# Power.net
KiCad netlist of a schematic drawn in Altium Designer
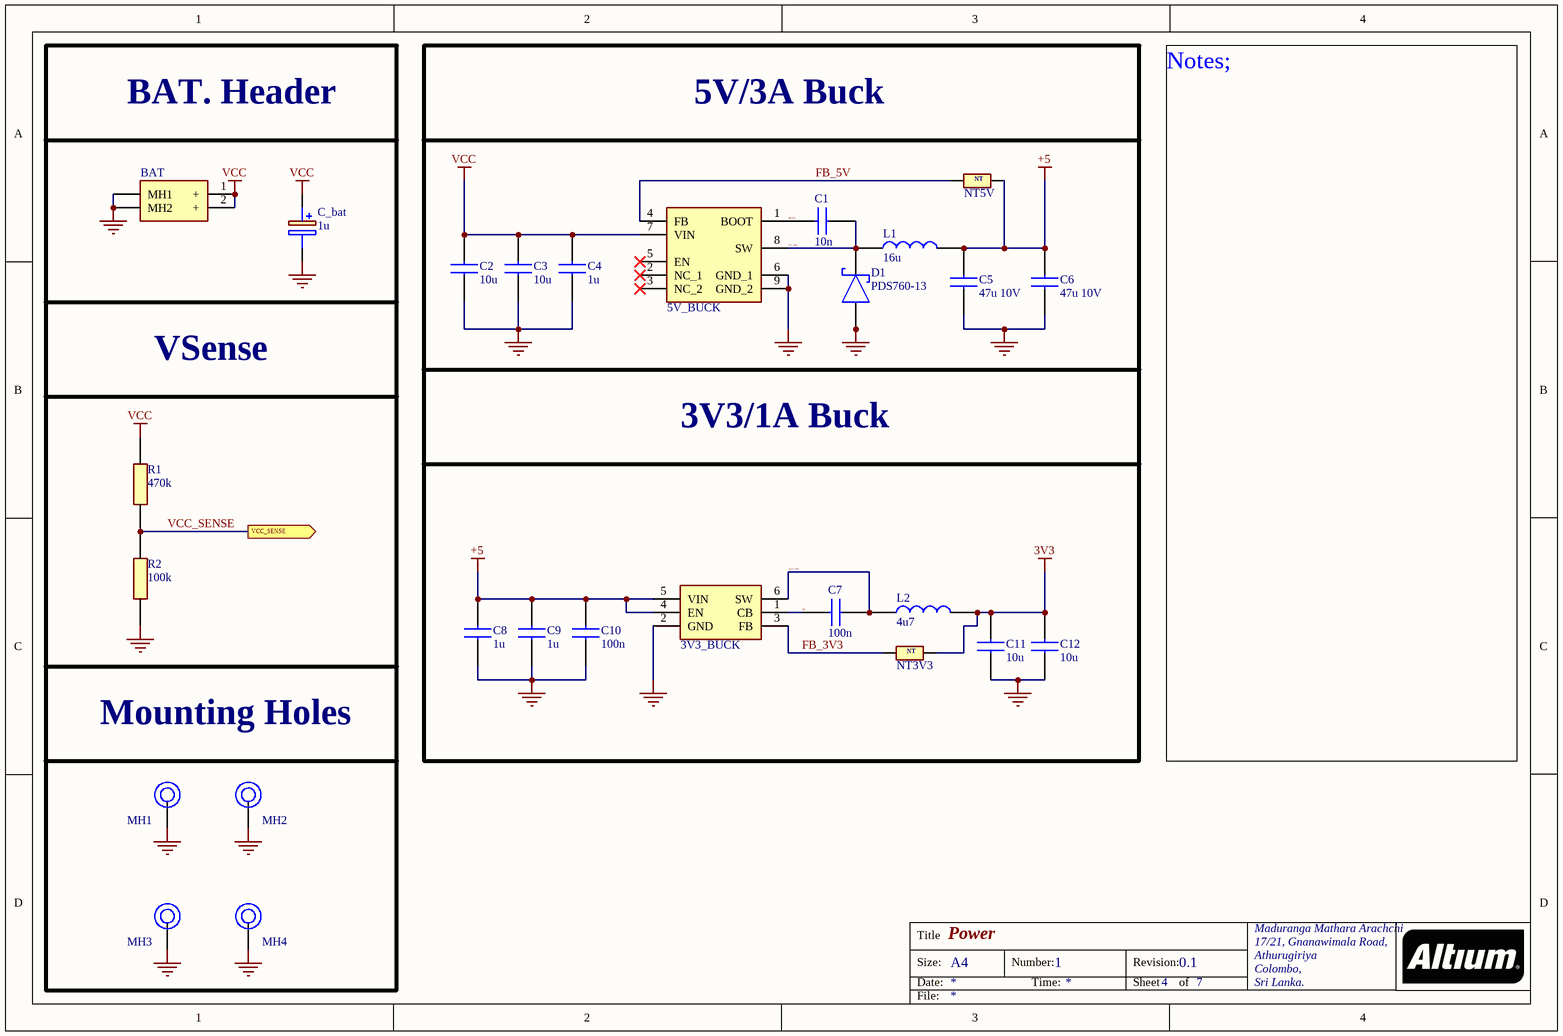
[diagram p0: Power.SchDoc]

(export (version "E")
  (design (tool "Eeschema 10.0.6"))
  (components
    (comp (ref "3V3_BUCK")
      (value "LMR50410Y3FQDBVRQ1")
      (footprint "RC_Car:SOT95P280X145-6N")
      (description "3V3 Buck")
      (fields (field (name "MOUSER PART NUMBER") "595-R50410Y3FQDBVRQ1"))
      (libsource (lib "RC_Car") (part "LMR50410Y3FQDBVRQ1"))
    )
    (comp (ref "5V_BUCK")
      (value "LM22676QMRX-5.0_NOPB")
      (footprint "RC_Car:SOIC127P600X170-9N")
      (description "5V Buck")
      (fields
        (field (name "MANUFACTURER_PART_NUMBER") "LM22676QMRX-5.0/NOPB")
        (field (name "MOUSER PART NUMBER") "926-LM22676QMRX50NPB")
      )
      (libsource (lib "RC_Car") (part "LM22676QMRX-5.0_NOPB"))
    )
    (comp (ref "BAT")
      (value "XT60PW-M")
      (footprint "RC_Car:XT60PWM")
      (description "Power Header")
      (libsource (lib "RC_Car") (part "XT60PW-M"))
    )
    (comp (ref "C1")
      (value "10n")
      (footprint "RC_Car:C0603")
      (description "Capacitor")
      (fields
        (field (name "MANUFACTURER_PART_NUMBER") "C0603C103K5RACTU")
        (field (name "MOUSER PART NUMBER") "80-C0603C103K5R")
      )
      (libsource (lib "RC_Car") (part "C0603C103K5RACTU"))
    )
    (comp (ref "C2")
      (value "10u")
      (footprint "RC_Car:CAPC1608X90N")
      (description "Capacitor")
      (fields (field (name "MANUFACTURER_PART_NUMBER") "C0603C106M9PAC-TU"))
      (libsource (lib "RC_Car") (part "C0603C106M9PAC-TU"))
    )
    (comp (ref "C3")
      (value "10u")
      (footprint "RC_Car:CAPC1608X90N")
      (description "Capacitor")
      (fields (field (name "MANUFACTURER_PART_NUMBER") "C0603C106M9PAC-TU"))
      (libsource (lib "RC_Car") (part "C0603C106M9PAC-TU"))
    )
    (comp (ref "C4")
      (value "1u")
      (footprint "RC_Car:CAPC1608X90N")
      (description "Capacitor")
      (fields
        (field (name "MANUFACTURER_PART_NUMBER") "MSASU168SB5105KTNA01")
        (field (name "MOUSER PART NUMBER") "963-MSASU168SB5105KT")
      )
      (libsource (lib "RC_Car") (part "MSASU168SB5105KTNA01"))
    )
    (comp (ref "C5")
      (value "47u 10V")
      (footprint "RC_Car:GRM32x")
      (description "Capacitor")
      (fields
        (field (name "MANUFACTURER_PART_NUMBER") "GRM32ER71A476KE15L")
        (field (name "MOUSER PART NUMBER") "81-GRM32ER71A476KE5L")
      )
      (libsource (lib "RC_Car") (part "GRM32ER71A476KE15L"))
    )
    (comp (ref "C6")
      (value "47u 10V")
      (footprint "RC_Car:GRM32x")
      (description "Capacitor")
      (fields
        (field (name "MANUFACTURER_PART_NUMBER") "GRM32ER71A476KE15L")
        (field (name "MOUSER PART NUMBER") "81-GRM32ER71A476KE5L")
      )
      (libsource (lib "RC_Car") (part "GRM32ER71A476KE15L"))
    )
    (comp (ref "C7")
      (value "100n")
      (footprint "RC_Car:GRM18x")
      (description "Capacitor")
      (fields
        (field (name "MANUFACTURER_PART_NUMBER") "GRM188R72A104KA35D")
        (field (name "MOUSER PART NUMBER") "81-GRM188R72A104KA35")
      )
      (libsource (lib "RC_Car") (part "GRM188R72A104KA35D"))
    )
    (comp (ref "C8")
      (value "1u")
      (footprint "RC_Car:CAPC1608X90N")
      (description "Capacitor")
      (fields
        (field (name "MANUFACTURER_PART_NUMBER") "MSASU168SB5105KTNA01")
        (field (name "MOUSER PART NUMBER") "963-MSASU168SB5105KT")
      )
      (libsource (lib "RC_Car") (part "MSASU168SB5105KTNA01"))
    )
    (comp (ref "C9")
      (value "1u")
      (footprint "RC_Car:CAPC1608X90N")
      (description "Capacitor")
      (fields
        (field (name "MANUFACTURER_PART_NUMBER") "MSASU168SB5105KTNA01")
        (field (name "MOUSER PART NUMBER") "963-MSASU168SB5105KT")
      )
      (libsource (lib "RC_Car") (part "MSASU168SB5105KTNA01"))
    )
    (comp (ref "C10")
      (value "100n")
      (footprint "RC_Car:GRM18x")
      (description "Capacitor")
      (fields
        (field (name "MANUFACTURER_PART_NUMBER") "GRM188R72A104KA35D")
        (field (name "MOUSER PART NUMBER") "81-GRM188R72A104KA35")
      )
      (libsource (lib "RC_Car") (part "GRM188R72A104KA35D"))
    )
    (comp (ref "C11")
      (value "10u")
      (footprint "RC_Car:CAPC1608X90N")
      (description "Capacitor")
      (fields (field (name "MANUFACTURER_PART_NUMBER") "C0603C106M9PAC-TU"))
      (libsource (lib "RC_Car") (part "C0603C106M9PAC-TU"))
    )
    (comp (ref "C12")
      (value "10u")
      (footprint "RC_Car:CAPC1608X90N")
      (description "Capacitor")
      (fields (field (name "MANUFACTURER_PART_NUMBER") "C0603C106M9PAC-TU"))
      (libsource (lib "RC_Car") (part "C0603C106M9PAC-TU"))
    )
    (comp (ref "C_bat")
      (value "1u")
      (footprint "RC_Car:CAPAE430X550N")
      (description "Capacitor Polarised")
      (fields
        (field (name "MANUFACTURER_PART_NUMBER") "865081740001")
        (field (name "MOUSER PART NUMBER") "710-865081740001")
      )
      (libsource (lib "RC_Car") (part "865081740001"))
    )
    (comp (ref "D1")
      (value "PDS760-13")
      (footprint "RC_Car:PDS76013")
      (description "Schottky Diode")
      (fields (field (name "MOUSER PART NUMBER") "621-PDS760-F"))
      (libsource (lib "RC_Car") (part "PDS760-13"))
    )
    (comp (ref "L1")
      (value "16u")
      (footprint "RC_Car:WE-HCI_105023")
      (description "Inductor")
      (fields
        (field (name "MANUFACTURER_PART_NUMBER") "7443251600")
        (field (name "MOUSER PART NUMBER") "710-7443251600")
      )
      (libsource (lib "RC_Car") (part "7443251600"))
    )
    (comp (ref "L2")
      (value "4u7")
      (footprint "RC_Car:SDR0403")
      (description "Inductor")
      (fields
        (field (name "MANUFACTURER_PART_NUMBER") "SDR0403-4R7ML")
        (field (name "MOUSER PART NUMBER") "652-SDR0403-4R7ML")
      )
      (libsource (lib "RC_Car") (part "SDR0403-4R7ML"))
    )
    (comp (ref "MH1")
      (value "Mounting Hole 2mm")
      (footprint "Mounting Hole")
      (libsource (lib "RC_Car") (part "Mounting Hole 2mm"))
    )
    (comp (ref "MH2")
      (value "Mounting Hole 2mm")
      (footprint "Mounting Hole")
      (libsource (lib "RC_Car") (part "Mounting Hole 2mm"))
    )
    (comp (ref "MH3")
      (value "Mounting Hole 2mm")
      (footprint "Mounting Hole")
      (libsource (lib "RC_Car") (part "Mounting Hole 2mm"))
    )
    (comp (ref "MH4")
      (value "Mounting Hole 2mm")
      (footprint "Mounting Hole")
      (libsource (lib "RC_Car") (part "Mounting Hole 2mm"))
    )
    (comp (ref "NT3V3")
      (value "NetTie_SMD")
      (footprint "NetTie_SMD")
      (libsource (lib "RC_Car") (part "NetTie_SMD"))
    )
    (comp (ref "NT5V")
      (value "NetTie_SMD")
      (footprint "NetTie_SMD")
      (libsource (lib "RC_Car") (part "NetTie_SMD"))
    )
    (comp (ref "R1")
      (value "470k")
      (footprint "RC_Car:ERJP03_PA3_(0603)")
      (description "Resistor")
      (fields
        (field (name "MANUFACTURER_PART_NUMBER") "ERJ-PA3F4703V")
        (field (name "MOUSER PART NUMBER") "667-ERJ-PA3F4703V")
      )
      (libsource (lib "RC_Car") (part "ERJ-PA3F4703V"))
    )
    (comp (ref "R2")
      (value "100k")
      (footprint "RC_Car:ERJP03_PA3_(0603)")
      (description "Resistor")
      (fields
        (field (name "MANUFACTURER_PART_NUMBER") "ERJ-PA3F1003V")
        (field (name "MOUSER PART NUMBER") "667-ERJ-PA3F1003V")
      )
      (libsource (lib "RC_Car") (part "ERJ-PA3F1003V"))
    )
  )
  (nets
    (net (code "1") (name "+5") (class "Default")
      (node (ref "3V3_BUCK") (pin "4") (pinfunction "EN_4") (pintype "passive"))
      (node (ref "3V3_BUCK") (pin "5") (pinfunction "VIN_5") (pintype "passive"))
      (node (ref "C10") (pin "2") (pinfunction "2_2") (pintype "passive"))
      (node (ref "C5") (pin "2") (pinfunction "2_2") (pintype "passive"))
      (node (ref "C6") (pin "2") (pinfunction "2_2") (pintype "passive"))
      (node (ref "C8") (pin "2") (pinfunction "2_2") (pintype "passive"))
      (node (ref "C9") (pin "2") (pinfunction "2_2") (pintype "passive"))
      (node (ref "L1") (pin "2") (pinfunction "2_2") (pintype "passive"))
      (node (ref "NT5V") (pin "2") (pinfunction "2_2") (pintype "passive"))
    )
    (net (code "2") (name "/3V3_SW") (class "Default")
      (node (ref "3V3_BUCK") (pin "6") (pinfunction "SW_6") (pintype "passive"))
      (node (ref "C7") (pin "2") (pinfunction "2_2") (pintype "passive"))
      (node (ref "L2") (pin "1") (pinfunction "1_1") (pintype "passive"))
    )
    (net (code "3") (name "/5V_SW") (class "Default")
      (node (ref "5V_BUCK") (pin "8") (pinfunction "SW_8") (pintype "passive"))
      (node (ref "C1") (pin "2") (pinfunction "2_2") (pintype "passive"))
      (node (ref "D1") (pin "3") (pinfunction "COM_K_3") (pintype "passive"))
      (node (ref "L1") (pin "1") (pinfunction "1_1") (pintype "passive"))
    )
    (net (code "4") (name "/BOOT") (class "Default")
      (node (ref "5V_BUCK") (pin "1") (pinfunction "BOOT_1") (pintype "passive"))
      (node (ref "C1") (pin "1") (pinfunction "1_1") (pintype "passive"))
    )
    (net (code "5") (name "/CB") (class "Default")
      (node (ref "3V3_BUCK") (pin "1") (pinfunction "CB_1") (pintype "passive"))
      (node (ref "C7") (pin "1") (pinfunction "1_1") (pintype "passive"))
    )
    (net (code "6") (name "/FB_3V3") (class "Default")
      (node (ref "3V3_BUCK") (pin "3") (pinfunction "FB_3") (pintype "passive"))
      (node (ref "NT3V3") (pin "1") (pinfunction "1_1") (pintype "passive"))
    )
    (net (code "7") (name "/FB_5V") (class "Default")
      (node (ref "5V_BUCK") (pin "4") (pinfunction "FB_4") (pintype "passive"))
      (node (ref "NT5V") (pin "1") (pinfunction "1_1") (pintype "passive"))
    )
    (net (code "8") (name "/VCC_SENSE") (class "Default")
      (node (ref "R1") (pin "2") (pinfunction "2_2") (pintype "passive"))
      (node (ref "R2") (pin "1") (pinfunction "1_1") (pintype "passive"))
    )
    (net (code "9") (name "3V3") (class "Default")
      (node (ref "C11") (pin "2") (pinfunction "2_2") (pintype "passive"))
      (node (ref "C12") (pin "2") (pinfunction "2_2") (pintype "passive"))
      (node (ref "L2") (pin "2") (pinfunction "2_2") (pintype "passive"))
      (node (ref "NT3V3") (pin "2") (pinfunction "2_2") (pintype "passive"))
    )
    (net (code "10") (name "GND") (class "Default")
      (node (ref "3V3_BUCK") (pin "2") (pinfunction "GND_2") (pintype "passive"))
      (node (ref "5V_BUCK") (pin "6") (pinfunction "GND_1_6") (pintype "passive"))
      (node (ref "5V_BUCK") (pin "9") (pinfunction "GND_2_9") (pintype "passive"))
      (node (ref "BAT") (pin "MH1") (pinfunction "MH1_MH1") (pintype "passive"))
      (node (ref "BAT") (pin "MH2") (pinfunction "MH2_MH2") (pintype "passive"))
      (node (ref "C10") (pin "1") (pinfunction "1_1") (pintype "passive"))
      (node (ref "C11") (pin "1") (pinfunction "1_1") (pintype "passive"))
      (node (ref "C12") (pin "1") (pinfunction "1_1") (pintype "passive"))
      (node (ref "C2") (pin "1") (pinfunction "1_1") (pintype "passive"))
      (node (ref "C3") (pin "1") (pinfunction "1_1") (pintype "passive"))
      (node (ref "C4") (pin "1") (pinfunction "1_1") (pintype "passive"))
      (node (ref "C5") (pin "1") (pinfunction "1_1") (pintype "passive"))
      (node (ref "C6") (pin "1") (pinfunction "1_1") (pintype "passive"))
      (node (ref "C8") (pin "1") (pinfunction "1_1") (pintype "passive"))
      (node (ref "C9") (pin "1") (pinfunction "1_1") (pintype "passive"))
      (node (ref "C_bat") (pin "2") (pinfunction "-_2") (pintype "passive"))
      (node (ref "D1") (pin "1") (pinfunction "A_1_1") (pintype "passive"))
      (node (ref "D1") (pin "2") (pinfunction "A_2_2") (pintype "passive"))
      (node (ref "MH1") (pin "1") (pinfunction "1_1") (pintype "passive"))
      (node (ref "MH2") (pin "1") (pinfunction "1_1") (pintype "passive"))
      (node (ref "MH3") (pin "1") (pinfunction "1_1") (pintype "passive"))
      (node (ref "MH4") (pin "1") (pinfunction "1_1") (pintype "passive"))
      (node (ref "R2") (pin "2") (pinfunction "2_2") (pintype "passive"))
    )
    (net (code "11") (name "VCC") (class "Default")
      (node (ref "5V_BUCK") (pin "7") (pinfunction "VIN_7") (pintype "passive"))
      (node (ref "BAT") (pin "1") (pinfunction "+_1") (pintype "passive"))
      (node (ref "BAT") (pin "2") (pinfunction "+_2") (pintype "passive"))
      (node (ref "C2") (pin "2") (pinfunction "2_2") (pintype "passive"))
      (node (ref "C3") (pin "2") (pinfunction "2_2") (pintype "passive"))
      (node (ref "C4") (pin "2") (pinfunction "2_2") (pintype "passive"))
      (node (ref "C_bat") (pin "1") (pinfunction "+_1") (pintype "passive"))
      (node (ref "R1") (pin "1") (pinfunction "1_1") (pintype "passive"))
    )
    (net (code "12") (name "unconnected-(5V_BUCK-EN-Pad5)") (class "Default")
      (node (ref "5V_BUCK") (pin "5") (pinfunction "EN_5") (pintype "passive+no_connect"))
    )
    (net (code "13") (name "unconnected-(5V_BUCK-NC_1-Pad2)") (class "Default")
      (node (ref "5V_BUCK") (pin "2") (pinfunction "NC_1_2") (pintype "passive+no_connect"))
    )
    (net (code "14") (name "unconnected-(5V_BUCK-NC_2-Pad3)") (class "Default")
      (node (ref "5V_BUCK") (pin "3") (pinfunction "NC_2_3") (pintype "passive+no_connect"))
    )
  )
)
